# Conn.net
KiCad netlist of a schematic drawn in Altium Designer
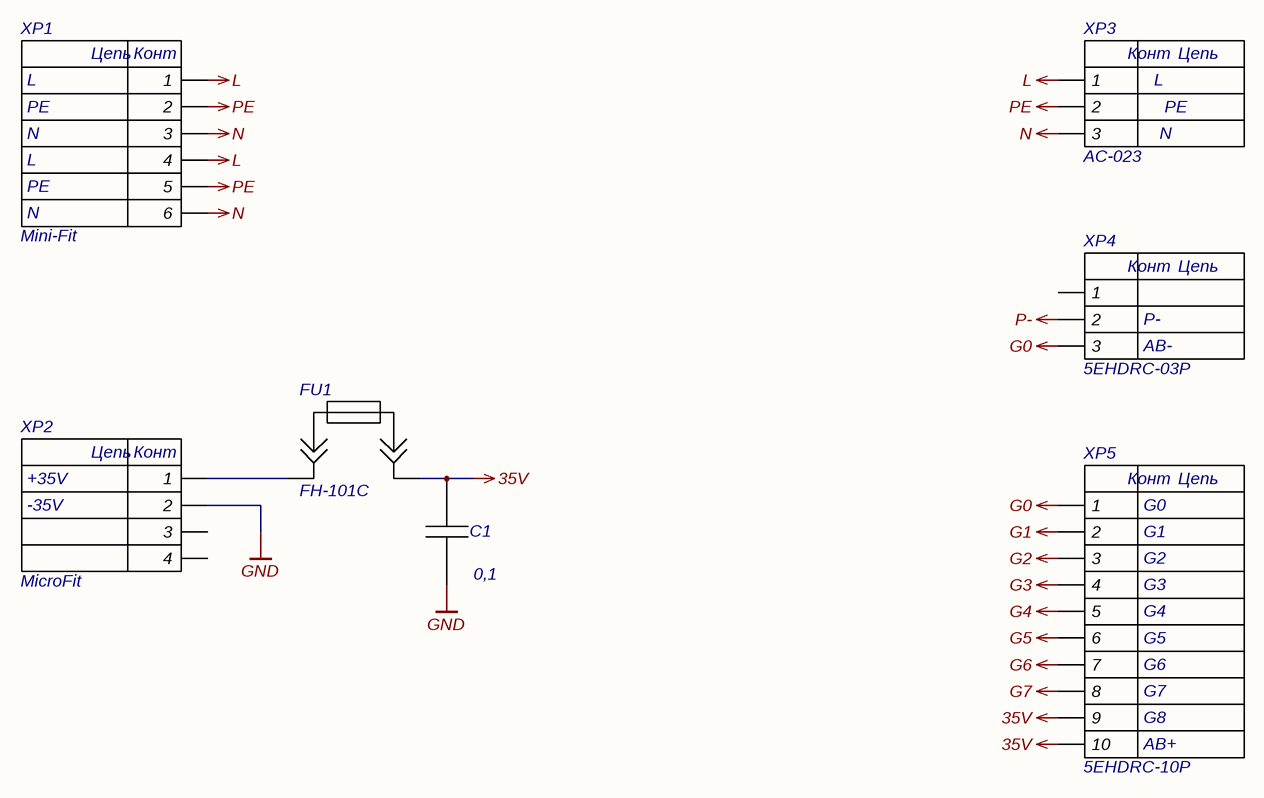
[diagram p0: Conn.SchDoc]

(export (version "E")
  (design (tool "Eeschema 10.0.6"))
  (components
    (comp (ref "C1")
      (value "0,1")
      (footprint "С0805")
      (description "Чип-конденсатор")
      (libsource (lib "Passive") (part "Chip Capasitor"))
    )
    (comp (ref "FU1")
      (value "FH-101C")
      (footprint "FH-101C")
      (description "Fuse holder 5x20mm")
      (fields (field (name "MANUFACTURER") "Dragon City Industries"))
      (libsource (lib "Schlib") (part "FH-101C"))
    )
    (comp (ref "XP1")
      (value "Mini-Fit")
      (footprint "MF2x3MA")
      (description "Mini-Fit 4,2mm A Male 6 pin")
      (fields
        (field (name "MANUFACTURER") "Connfly Electronic Co.")
        (field (name "P6") "N")
        (field (name "P5") "PE")
        (field (name "P4") "L")
        (field (name "P3") "N")
        (field (name "P2") "PE")
        (field (name "P1") "L")
      )
      (libsource (lib "Schlib") (part "MF2x3MA"))
    )
    (comp (ref "XP2")
      (value "MicroFit")
      (footprint "MF3-04MA")
      (description "MicroFit 3mm RA Male 4 pin")
      (fields
        (field (name "MANUFACTURER") "Molex Incorporated")
        (field (name "P2") "-35V")
        (field (name "P1") "+35V")
      )
      (libsource (lib "Schlib") (part "43045-0412"))
    )
    (comp (ref "XP3")
      (value "AC-023")
      (footprint "IEC-C14")
      (description "Разъём питания AC, одинарный")
      (fields (field (name "MANUFACTURER") "RUICHI"))
      (libsource (lib "Schlib") (part "AC-023"))
    )
    (comp (ref "XP4")
      (value "5EHDRC-03P")
      (footprint "5EHDRC-03P")
      (description "Клеммник 3 конт. \"вилка\" шаг 5.00 мм")
      (fields
        (field (name "MANUFACTURER") "Dinkle Enterprise")
        (field (name "P2") "P-")
        (field (name "P3") "AB-")
      )
      (libsource (lib "Schlib") (part "5EHDRC-03P"))
    )
    (comp (ref "XP5")
      (value "5EHDRC-10P")
      (footprint "5EHDRC-10P")
      (description "Клеммник 10 конт. \"вилка\" шаг 5.00 мм")
      (fields
        (field (name "MANUFACTURER") "Dinkle Enterprise")
        (field (name "P6") "G5")
        (field (name "P1") "G0")
        (field (name "P2") "G1")
        (field (name "P3") "G2")
        (field (name "P4") "G3")
        (field (name "P5") "G4")
        (field (name "P7") "G6")
        (field (name "P8") "G7")
        (field (name "P9") "G8")
        (field (name "P10") "AB+")
      )
      (libsource (lib "Schlib") (part "5EHDRC-10P"))
    )
  )
  (nets
    (net (code "1") (name "35V") (class "Default")
      (node (ref "C1") (pin "2") (pinfunction "2_2") (pintype "passive"))
      (node (ref "FU1") (pin "2") (pinfunction "2_2") (pintype "passive"))
      (node (ref "XP5") (pin "10") (pinfunction "10_10") (pintype "passive"))
      (node (ref "XP5") (pin "9") (pinfunction "9_9") (pintype "passive"))
    )
    (net (code "2") (name "G0") (class "Default")
      (node (ref "XP4") (pin "3") (pinfunction "3_3") (pintype "passive"))
      (node (ref "XP5") (pin "1") (pinfunction "1_1") (pintype "passive"))
    )
    (net (code "3") (name "G1") (class "Default")
      (node (ref "XP5") (pin "2") (pinfunction "2_2") (pintype "passive"))
    )
    (net (code "4") (name "G2") (class "Default")
      (node (ref "XP5") (pin "3") (pinfunction "3_3") (pintype "passive"))
    )
    (net (code "5") (name "G3") (class "Default")
      (node (ref "XP5") (pin "4") (pinfunction "4_4") (pintype "passive"))
    )
    (net (code "6") (name "G4") (class "Default")
      (node (ref "XP5") (pin "5") (pinfunction "5_5") (pintype "passive"))
    )
    (net (code "7") (name "G5") (class "Default")
      (node (ref "XP5") (pin "6") (pinfunction "6_6") (pintype "passive"))
    )
    (net (code "8") (name "G6") (class "Default")
      (node (ref "XP5") (pin "7") (pinfunction "7_7") (pintype "passive"))
    )
    (net (code "9") (name "G7") (class "Default")
      (node (ref "XP5") (pin "8") (pinfunction "8_8") (pintype "passive"))
    )
    (net (code "10") (name "GND") (class "Default")
      (node (ref "C1") (pin "1") (pinfunction "1_1") (pintype "passive"))
      (node (ref "XP2") (pin "2") (pinfunction "2_2") (pintype "passive"))
    )
    (net (code "11") (name "L") (class "Default")
      (node (ref "XP1") (pin "1") (pinfunction "1_1") (pintype "passive"))
      (node (ref "XP1") (pin "4") (pinfunction "4_4") (pintype "passive"))
      (node (ref "XP3") (pin "1") (pinfunction "1_1") (pintype "passive"))
    )
    (net (code "12") (name "N") (class "Default")
      (node (ref "XP1") (pin "3") (pinfunction "3_3") (pintype "passive"))
      (node (ref "XP1") (pin "6") (pinfunction "6_6") (pintype "passive"))
      (node (ref "XP3") (pin "3") (pinfunction "3_3") (pintype "passive"))
    )
    (net (code "13") (name "Net-(FU1-Pad1)") (class "Default")
      (node (ref "FU1") (pin "1") (pinfunction "1_1") (pintype "passive"))
      (node (ref "XP2") (pin "1") (pinfunction "1_1") (pintype "passive"))
    )
    (net (code "14") (name "P-") (class "Default")
      (node (ref "XP4") (pin "2") (pinfunction "2_2") (pintype "passive"))
    )
    (net (code "15") (name "PE") (class "Default")
      (node (ref "XP1") (pin "2") (pinfunction "2_2") (pintype "passive"))
      (node (ref "XP1") (pin "5") (pinfunction "5_5") (pintype "passive"))
      (node (ref "XP3") (pin "2") (pinfunction "2_2") (pintype "passive"))
    )
    (net (code "16") (name "unconnected-(XP2-Pad3)") (class "Default")
      (node (ref "XP2") (pin "3") (pinfunction "3_3") (pintype "passive"))
    )
    (net (code "17") (name "unconnected-(XP2-Pad4)") (class "Default")
      (node (ref "XP2") (pin "4") (pinfunction "4_4") (pintype "passive"))
    )
    (net (code "18") (name "unconnected-(XP4-Pad1)") (class "Default")
      (node (ref "XP4") (pin "1") (pinfunction "1_1") (pintype "passive"))
    )
  )
)
